# Laser7Clock.net
KiCad netlist of a schematic drawn in EAGLE
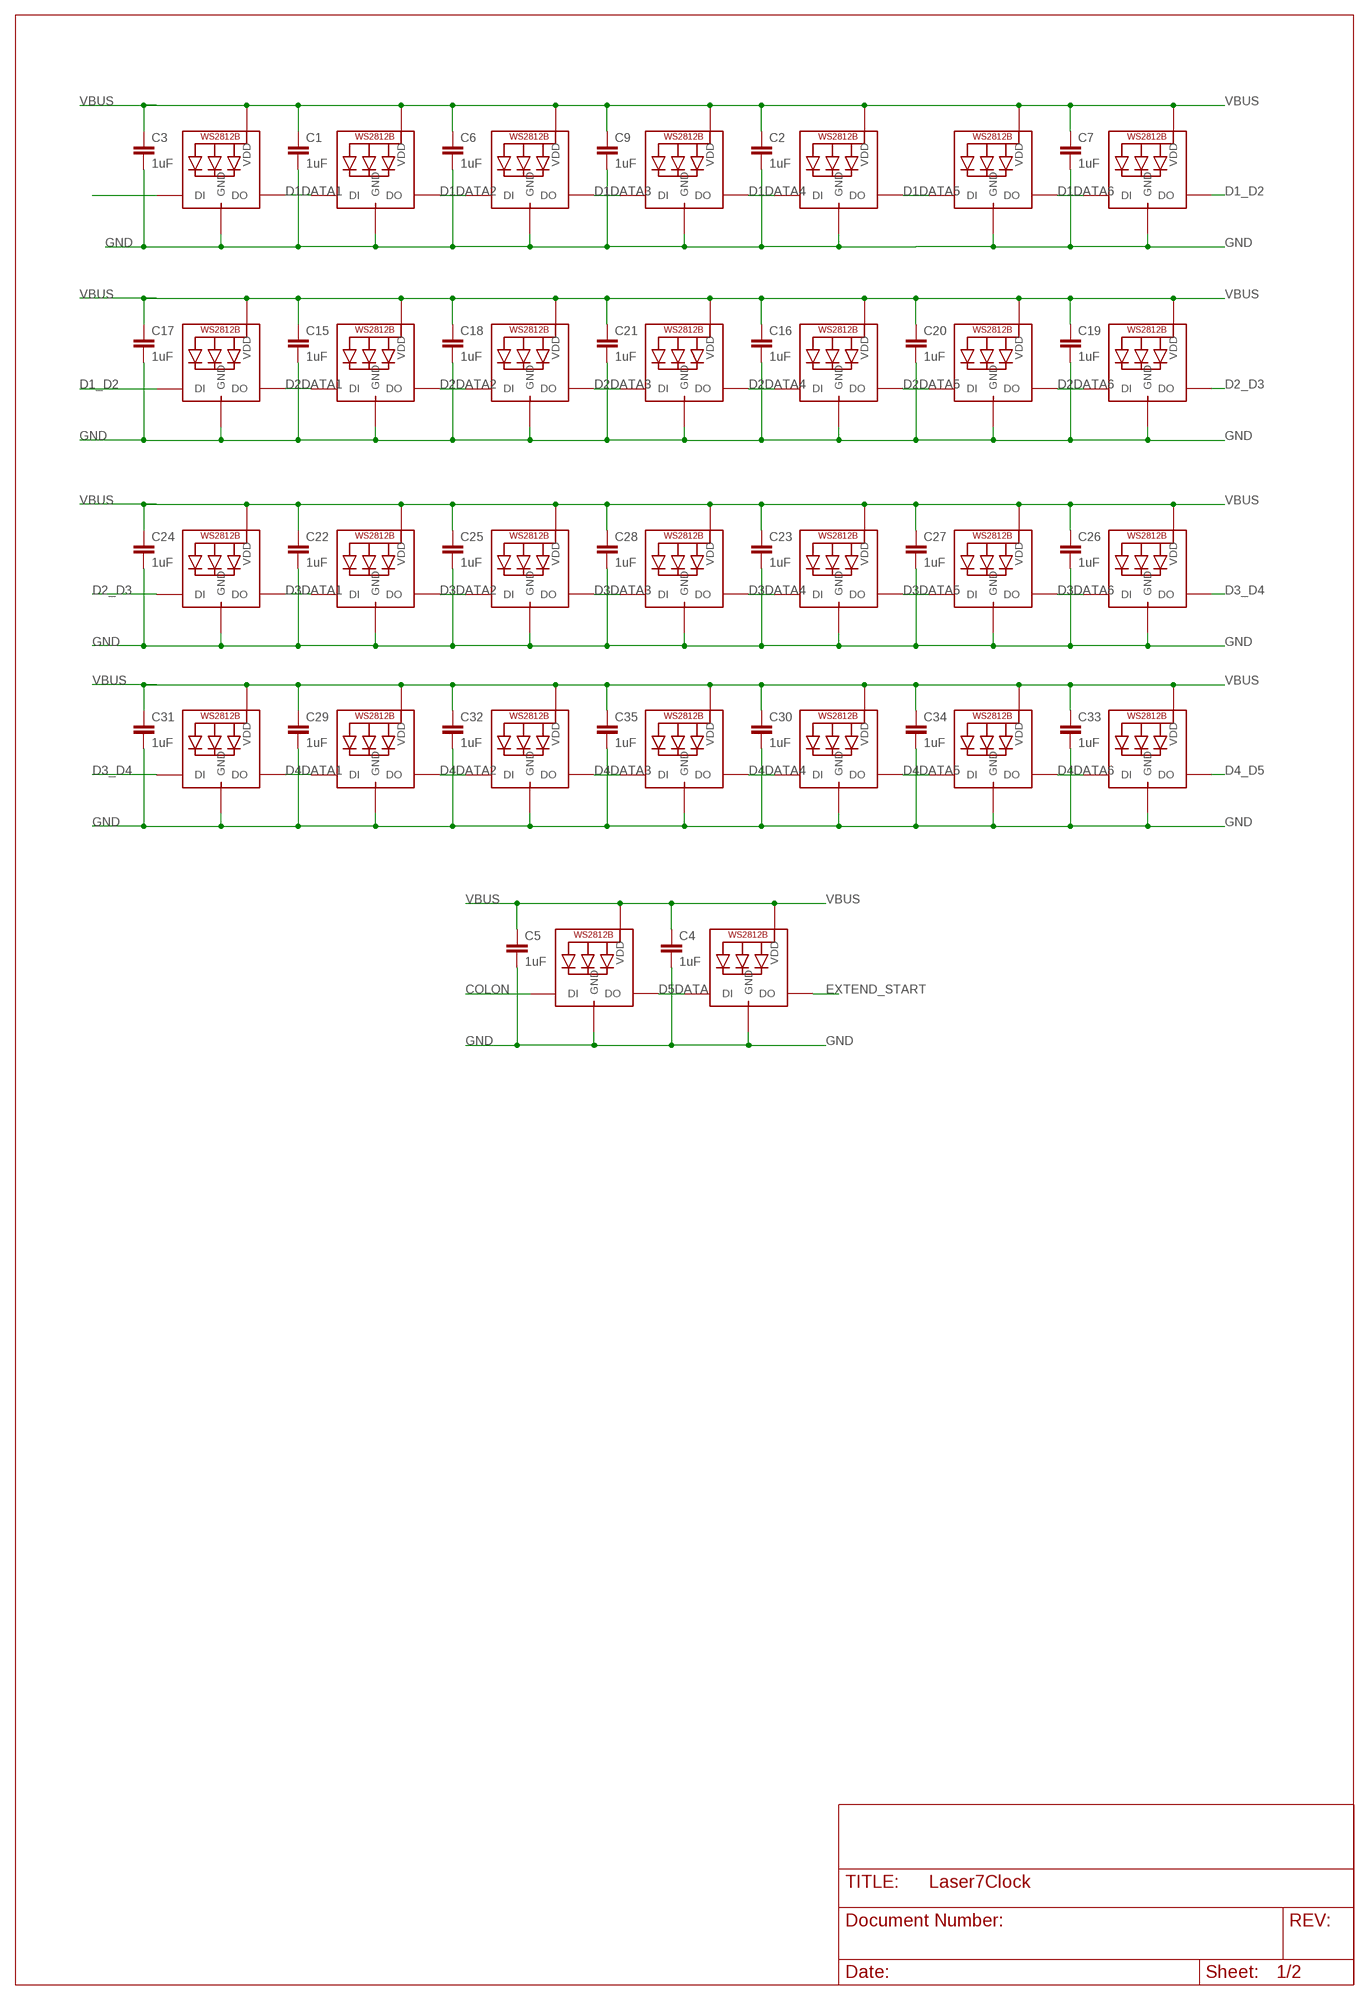
[diagram p0: schematic, sheet 1]
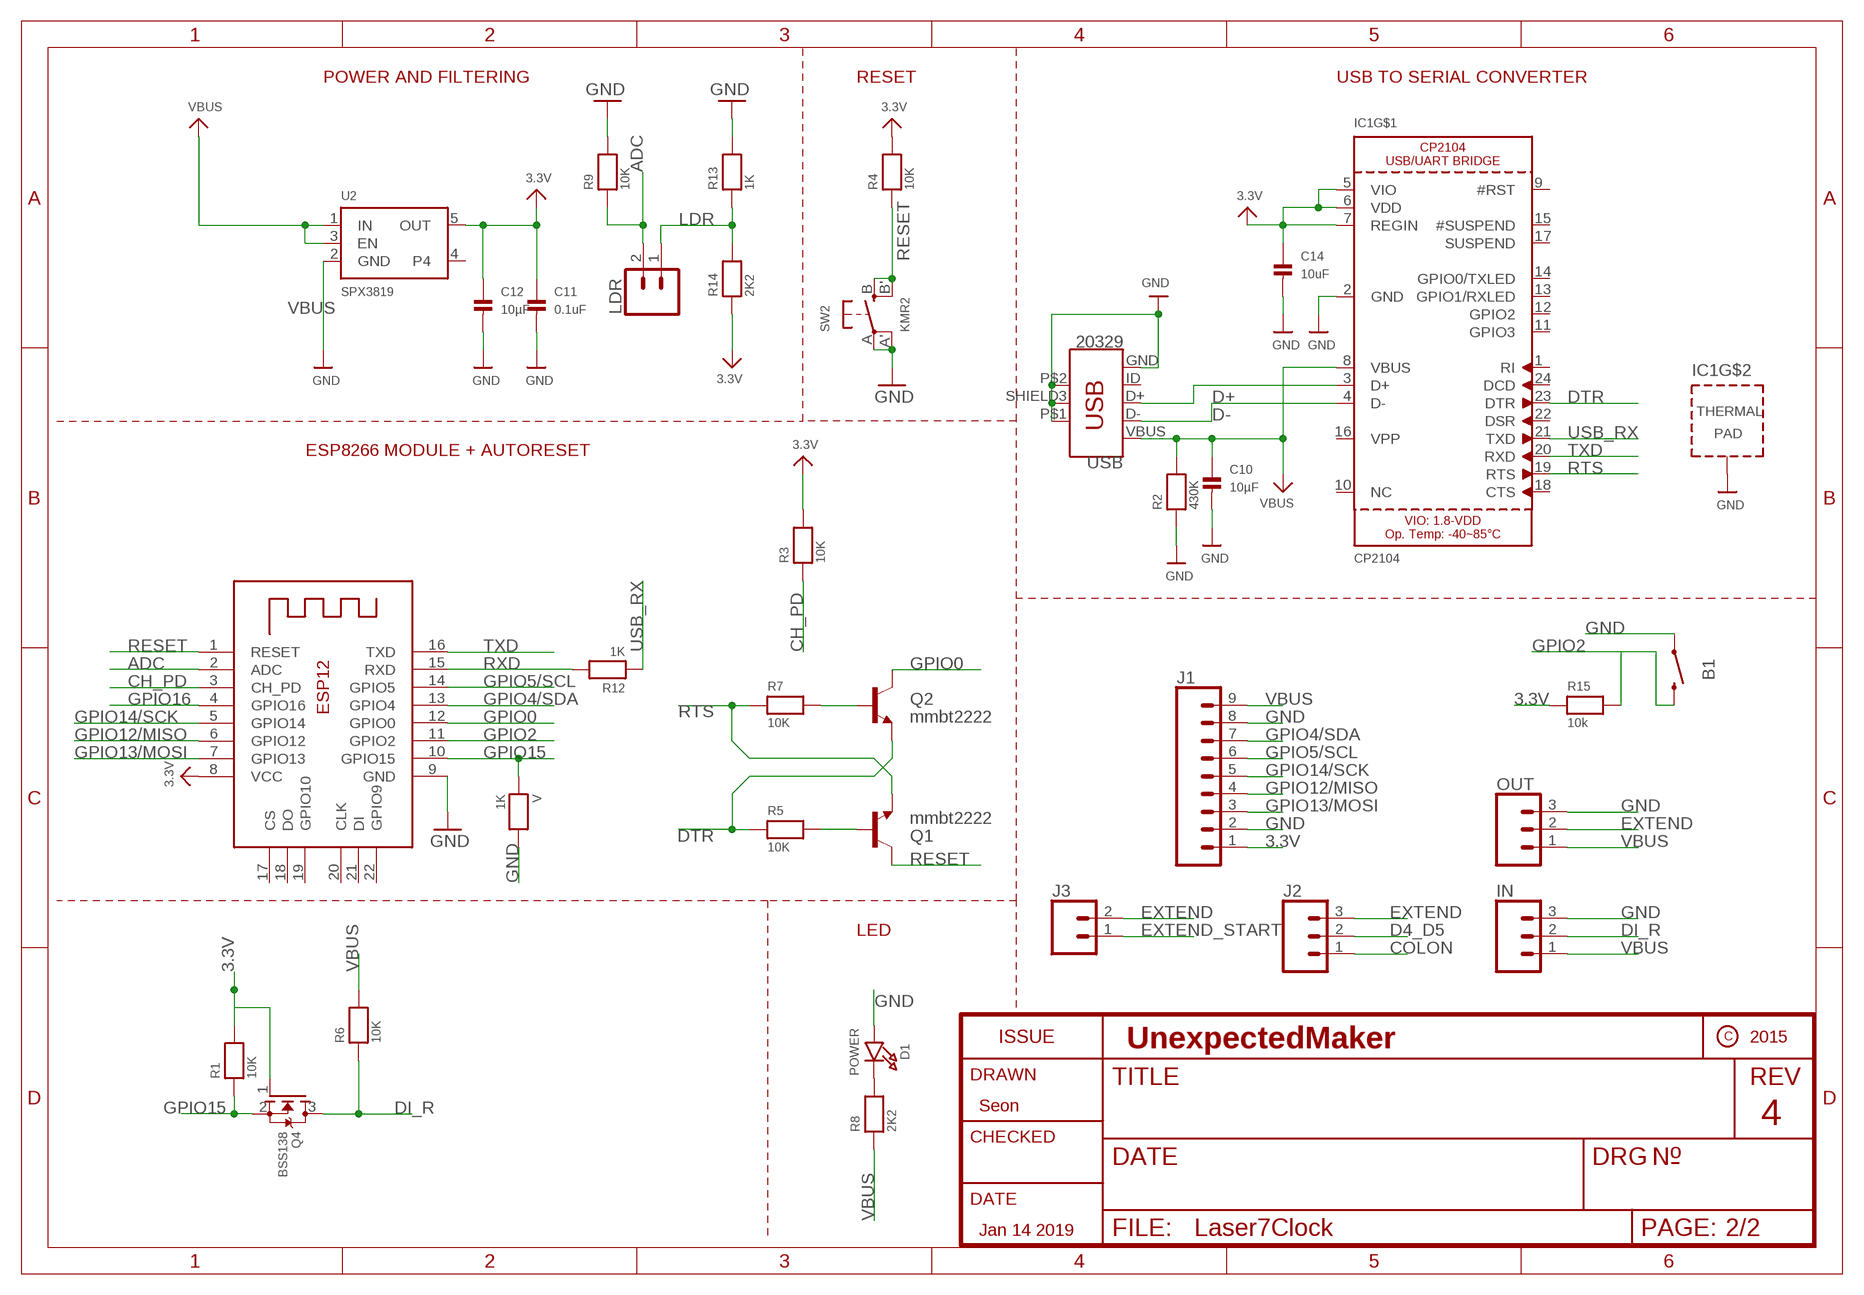
[diagram p1: schematic, sheet 2]

(export (version "E")
  (design (tool "Eeschema 10.0.6"))
  (components
    (comp (ref "B1")
      (value "MOMENTARY-SWITCH-SPST-PTH-RIGHT-ANGLE-KIT")
      (footprint "eagle-import:TACTILE_SWITCH_PTH_RIGHT_ANGLE_KIT")
      (libsource (lib "eagle-import") (part "MOMENTARY-SWITCH-SPST-PTH-RIGHT-ANGLE-KIT"))
    )
    (comp (ref "C10")
      (value "10µF")
      (footprint "eagle-import:_0805MP")
      (libsource (lib "eagle-import") (part "CAP_CERAMIC_0805MP"))
    )
    (comp (ref "C11")
      (value "0.1uF")
      (footprint "eagle-import:_0805MP")
      (libsource (lib "eagle-import") (part "CAP_CERAMIC_0805MP"))
    )
    (comp (ref "C12")
      (value "10µF")
      (footprint "eagle-import:_0805MP")
      (libsource (lib "eagle-import") (part "CAP_CERAMIC_0805MP"))
    )
    (comp (ref "C14")
      (value "10uF")
      (footprint "eagle-import:_0805MP")
      (libsource (lib "eagle-import") (part "CAP_CERAMIC_0805MP"))
    )
    (comp (ref "D1")
      (value "POWER")
      (footprint "eagle-import:CHIPLED_0805_NOOUTLINE")
      (libsource (lib "eagle-import") (part "LED0805_NOOUTLINE"))
    )
    (comp (ref "IC1")
      (value "CP2104")
      (footprint "eagle-import:QFN24_4MM_SMSC")
      (libsource (lib "eagle-import") (part "CP2104"))
    )
    (comp (ref "IN")
      (value "CONN_03LONGPADS")
      (footprint "eagle-import:1X03_LONGPADS")
      (libsource (lib "eagle-import") (part "CONN_03LONGPADS"))
    )
    (comp (ref "J1")
      (value "CONN_09NO_SILK")
      (footprint "eagle-import:1X09_NO_SILK")
      (libsource (lib "eagle-import") (part "CONN_09NO_SILK"))
    )
    (comp (ref "J2")
      (value "CONN_031X03_NO_SILK")
      (footprint "eagle-import:1X03_NO_SILK")
      (libsource (lib "eagle-import") (part "CONN_031X03_NO_SILK"))
    )
    (comp (ref "J3")
      (value "CONN_021X02_NO_SILK")
      (footprint "eagle-import:1X02_NO_SILK")
      (libsource (lib "eagle-import") (part "CONN_021X02_NO_SILK"))
    )
    (comp (ref "LDR")
      (value "CONN_021X02_NO_SILK")
      (footprint "eagle-import:1X02_NO_SILK")
      (libsource (lib "eagle-import") (part "CONN_021X02_NO_SILK"))
    )
    (comp (ref "OUT")
      (value "CONN_03LONGPADS")
      (footprint "eagle-import:1X03_LONGPADS")
      (libsource (lib "eagle-import") (part "CONN_03LONGPADS"))
    )
    (comp (ref "Q1")
      (value "mmbt2222")
      (footprint "eagle-import:SOT23-3")
      (libsource (lib "eagle-import") (part "TRANSISTOR_NPNSOT23-3"))
    )
    (comp (ref "Q2")
      (value "mmbt2222")
      (footprint "eagle-import:SOT23-3")
      (libsource (lib "eagle-import") (part "TRANSISTOR_NPNSOT23-3"))
    )
    (comp (ref "Q4")
      (value "BSS138")
      (footprint "eagle-import:SOT23-R")
      (libsource (lib "eagle-import") (part "MOSFET-NREFLOW"))
    )
    (comp (ref "R1")
      (value "10K")
      (footprint "eagle-import:_0603MP")
      (libsource (lib "eagle-import") (part "RESISTOR_0603MP"))
    )
    (comp (ref "R2")
      (value "430K")
      (footprint "eagle-import:_0805MP")
      (libsource (lib "eagle-import") (part "RESISTOR_0805MP"))
    )
    (comp (ref "R3")
      (value "10K")
      (footprint "eagle-import:_0603MP")
      (libsource (lib "eagle-import") (part "RESISTOR_0603MP"))
    )
    (comp (ref "R4")
      (value "10K")
      (footprint "eagle-import:_0603MP")
      (libsource (lib "eagle-import") (part "RESISTOR_0603MP"))
    )
    (comp (ref "R5")
      (value "10K")
      (footprint "eagle-import:_0603MP")
      (libsource (lib "eagle-import") (part "RESISTOR_0603MP"))
    )
    (comp (ref "R6")
      (value "10K")
      (footprint "eagle-import:_0603MP")
      (libsource (lib "eagle-import") (part "RESISTOR_0603MP"))
    )
    (comp (ref "R7")
      (value "10K")
      (footprint "eagle-import:_0603MP")
      (libsource (lib "eagle-import") (part "RESISTOR_0603MP"))
    )
    (comp (ref "R8")
      (value "2K2")
      (footprint "eagle-import:_0805MP")
      (libsource (lib "eagle-import") (part "RESISTOR_0805MP"))
    )
    (comp (ref "R9")
      (value "10K")
      (footprint "eagle-import:_0805MP")
      (libsource (lib "eagle-import") (part "RESISTOR_0805MP"))
    )
    (comp (ref "R12")
      (value "1K")
      (footprint "eagle-import:_0603MP")
      (libsource (lib "eagle-import") (part "RESISTOR_0603MP"))
    )
    (comp (ref "R13")
      (value "1K")
      (footprint "eagle-import:_0805MP")
      (libsource (lib "eagle-import") (part "RESISTOR_0805MP"))
    )
    (comp (ref "R14")
      (value "2K2")
      (footprint "eagle-import:_0805MP")
      (libsource (lib "eagle-import") (part "RESISTOR_0805MP"))
    )
    (comp (ref "R15")
      (value "10k")
      (footprint "eagle-import:_0603MP")
      (libsource (lib "eagle-import") (part "RESISTOR_0603MP"))
    )
    (comp (ref "SW2")
      (value "KMR2")
      (footprint "eagle-import:BTN_KMR2_4.6X2.8")
      (libsource (lib "eagle-import") (part "SWITCH_TACT_SMT4.6X2.8"))
    )
    (comp (ref "U2")
      (value "SPX3819")
      (footprint "eagle-import:SOT23-5")
      (libsource (lib "eagle-import") (part "VREG_SOT23-5"))
    )
    (comp (ref "USB")
      (value "20329")
      (footprint "eagle-import:USB-B-MICRO-SMD")
      (libsource (lib "eagle-import") (part "TINYPICO_USB_FEMALE-SMT"))
    )
    (comp (ref "V")
      (value "1K")
      (footprint "eagle-import:_0603MP")
      (libsource (lib "eagle-import") (part "RESISTOR_0603MP"))
    )
    (comp (ref "X2")
      (value "ESP-12")
      (footprint "eagle-import:ESP-12E")
      (libsource (lib "eagle-import") (part "ESP-12E"))
    )
    (comp (ref "C1")
      (value "1uF")
      (footprint "eagle-import:C0805K")
      (libsource (lib "eagle-import") (part "C-EUC0805K"))
    )
    (comp (ref "C2")
      (value "1uF")
      (footprint "eagle-import:C0805K")
      (libsource (lib "eagle-import") (part "C-EUC0805K"))
    )
    (comp (ref "C3")
      (value "1uF")
      (footprint "eagle-import:C0805K")
      (libsource (lib "eagle-import") (part "C-EUC0805K"))
    )
    (comp (ref "C4")
      (value "1uF")
      (footprint "eagle-import:C0805K")
      (libsource (lib "eagle-import") (part "C-EUC0805K"))
    )
    (comp (ref "C5")
      (value "1uF")
      (footprint "eagle-import:C0805K")
      (libsource (lib "eagle-import") (part "C-EUC0805K"))
    )
    (comp (ref "C6")
      (value "1uF")
      (footprint "eagle-import:C0805K")
      (libsource (lib "eagle-import") (part "C-EUC0805K"))
    )
    (comp (ref "C7")
      (value "1uF")
      (footprint "eagle-import:C0805K")
      (libsource (lib "eagle-import") (part "C-EUC0805K"))
    )
    (comp (ref "C9")
      (value "1uF")
      (footprint "eagle-import:C0805K")
      (libsource (lib "eagle-import") (part "C-EUC0805K"))
    )
    (comp (ref "C15")
      (value "1uF")
      (footprint "eagle-import:C0805K")
      (libsource (lib "eagle-import") (part "C-EUC0805K"))
    )
    (comp (ref "C16")
      (value "1uF")
      (footprint "eagle-import:C0805K")
      (libsource (lib "eagle-import") (part "C-EUC0805K"))
    )
    (comp (ref "C17")
      (value "1uF")
      (footprint "eagle-import:C0805K")
      (libsource (lib "eagle-import") (part "C-EUC0805K"))
    )
    (comp (ref "C18")
      (value "1uF")
      (footprint "eagle-import:C0805K")
      (libsource (lib "eagle-import") (part "C-EUC0805K"))
    )
    (comp (ref "C19")
      (value "1uF")
      (footprint "eagle-import:C0805K")
      (libsource (lib "eagle-import") (part "C-EUC0805K"))
    )
    (comp (ref "C20")
      (value "1uF")
      (footprint "eagle-import:C0805K")
      (libsource (lib "eagle-import") (part "C-EUC0805K"))
    )
    (comp (ref "C21")
      (value "1uF")
      (footprint "eagle-import:C0805K")
      (libsource (lib "eagle-import") (part "C-EUC0805K"))
    )
    (comp (ref "C22")
      (value "1uF")
      (footprint "eagle-import:C0805K")
      (libsource (lib "eagle-import") (part "C-EUC0805K"))
    )
    (comp (ref "C23")
      (value "1uF")
      (footprint "eagle-import:C0805K")
      (libsource (lib "eagle-import") (part "C-EUC0805K"))
    )
    (comp (ref "C24")
      (value "1uF")
      (footprint "eagle-import:C0805K")
      (libsource (lib "eagle-import") (part "C-EUC0805K"))
    )
    (comp (ref "C25")
      (value "1uF")
      (footprint "eagle-import:C0805K")
      (libsource (lib "eagle-import") (part "C-EUC0805K"))
    )
    (comp (ref "C26")
      (value "1uF")
      (footprint "eagle-import:C0805K")
      (libsource (lib "eagle-import") (part "C-EUC0805K"))
    )
    (comp (ref "C27")
      (value "1uF")
      (footprint "eagle-import:C0805K")
      (libsource (lib "eagle-import") (part "C-EUC0805K"))
    )
    (comp (ref "C28")
      (value "1uF")
      (footprint "eagle-import:C0805K")
      (libsource (lib "eagle-import") (part "C-EUC0805K"))
    )
    (comp (ref "C29")
      (value "1uF")
      (footprint "eagle-import:C0805K")
      (libsource (lib "eagle-import") (part "C-EUC0805K"))
    )
    (comp (ref "C30")
      (value "1uF")
      (footprint "eagle-import:C0805K")
      (libsource (lib "eagle-import") (part "C-EUC0805K"))
    )
    (comp (ref "C31")
      (value "1uF")
      (footprint "eagle-import:C0805K")
      (libsource (lib "eagle-import") (part "C-EUC0805K"))
    )
    (comp (ref "C32")
      (value "1uF")
      (footprint "eagle-import:C0805K")
      (libsource (lib "eagle-import") (part "C-EUC0805K"))
    )
    (comp (ref "C33")
      (value "1uF")
      (footprint "eagle-import:C0805K")
      (libsource (lib "eagle-import") (part "C-EUC0805K"))
    )
    (comp (ref "C34")
      (value "1uF")
      (footprint "eagle-import:C0805K")
      (libsource (lib "eagle-import") (part "C-EUC0805K"))
    )
    (comp (ref "C35")
      (value "1uF")
      (footprint "eagle-import:C0805K")
      (libsource (lib "eagle-import") (part "C-EUC0805K"))
    )
    (comp (ref "D1L1")
      (value "WS2812B5050")
      (footprint "eagle-import:WS2812B")
      (libsource (lib "eagle-import") (part "WS2812B5050"))
    )
    (comp (ref "D1L2")
      (value "WS2812B5050")
      (footprint "eagle-import:WS2812B")
      (libsource (lib "eagle-import") (part "WS2812B5050"))
    )
    (comp (ref "D1L3")
      (value "WS2812B5050")
      (footprint "eagle-import:WS2812B")
      (libsource (lib "eagle-import") (part "WS2812B5050"))
    )
    (comp (ref "D1L4")
      (value "WS2812B5050")
      (footprint "eagle-import:WS2812B")
      (libsource (lib "eagle-import") (part "WS2812B5050"))
    )
    (comp (ref "D1L5")
      (value "WS2812B5050")
      (footprint "eagle-import:WS2812B")
      (libsource (lib "eagle-import") (part "WS2812B5050"))
    )
    (comp (ref "D1L6")
      (value "WS2812B5050")
      (footprint "eagle-import:WS2812B")
      (libsource (lib "eagle-import") (part "WS2812B5050"))
    )
    (comp (ref "D1L7")
      (value "WS2812B5050")
      (footprint "eagle-import:WS2812B")
      (libsource (lib "eagle-import") (part "WS2812B5050"))
    )
    (comp (ref "D2L1")
      (value "WS2812B5050")
      (footprint "eagle-import:WS2812B")
      (libsource (lib "eagle-import") (part "WS2812B5050"))
    )
    (comp (ref "D2L2")
      (value "WS2812B5050")
      (footprint "eagle-import:WS2812B")
      (libsource (lib "eagle-import") (part "WS2812B5050"))
    )
    (comp (ref "D2L3")
      (value "WS2812B5050")
      (footprint "eagle-import:WS2812B")
      (libsource (lib "eagle-import") (part "WS2812B5050"))
    )
    (comp (ref "D2L4")
      (value "WS2812B5050")
      (footprint "eagle-import:WS2812B")
      (libsource (lib "eagle-import") (part "WS2812B5050"))
    )
    (comp (ref "D2L5")
      (value "WS2812B5050")
      (footprint "eagle-import:WS2812B")
      (libsource (lib "eagle-import") (part "WS2812B5050"))
    )
    (comp (ref "D2L6")
      (value "WS2812B5050")
      (footprint "eagle-import:WS2812B")
      (libsource (lib "eagle-import") (part "WS2812B5050"))
    )
    (comp (ref "D2L7")
      (value "WS2812B5050")
      (footprint "eagle-import:WS2812B")
      (libsource (lib "eagle-import") (part "WS2812B5050"))
    )
    (comp (ref "D3L1")
      (value "WS2812B5050")
      (footprint "eagle-import:WS2812B")
      (libsource (lib "eagle-import") (part "WS2812B5050"))
    )
    (comp (ref "D3L2")
      (value "WS2812B5050")
      (footprint "eagle-import:WS2812B")
      (libsource (lib "eagle-import") (part "WS2812B5050"))
    )
    (comp (ref "D3L3")
      (value "WS2812B5050")
      (footprint "eagle-import:WS2812B")
      (libsource (lib "eagle-import") (part "WS2812B5050"))
    )
    (comp (ref "D3L4")
      (value "WS2812B5050")
      (footprint "eagle-import:WS2812B")
      (libsource (lib "eagle-import") (part "WS2812B5050"))
    )
    (comp (ref "D3L5")
      (value "WS2812B5050")
      (footprint "eagle-import:WS2812B")
      (libsource (lib "eagle-import") (part "WS2812B5050"))
    )
    (comp (ref "D3L6")
      (value "WS2812B5050")
      (footprint "eagle-import:WS2812B")
      (libsource (lib "eagle-import") (part "WS2812B5050"))
    )
    (comp (ref "D3L7")
      (value "WS2812B5050")
      (footprint "eagle-import:WS2812B")
      (libsource (lib "eagle-import") (part "WS2812B5050"))
    )
    (comp (ref "D4L1")
      (value "WS2812B5050")
      (footprint "eagle-import:WS2812B")
      (libsource (lib "eagle-import") (part "WS2812B5050"))
    )
    (comp (ref "D4L2")
      (value "WS2812B5050")
      (footprint "eagle-import:WS2812B")
      (libsource (lib "eagle-import") (part "WS2812B5050"))
    )
    (comp (ref "D4L3")
      (value "WS2812B5050")
      (footprint "eagle-import:WS2812B")
      (libsource (lib "eagle-import") (part "WS2812B5050"))
    )
    (comp (ref "D4L4")
      (value "WS2812B5050")
      (footprint "eagle-import:WS2812B")
      (libsource (lib "eagle-import") (part "WS2812B5050"))
    )
    (comp (ref "D4L5")
      (value "WS2812B5050")
      (footprint "eagle-import:WS2812B")
      (libsource (lib "eagle-import") (part "WS2812B5050"))
    )
    (comp (ref "D4L6")
      (value "WS2812B5050")
      (footprint "eagle-import:WS2812B")
      (libsource (lib "eagle-import") (part "WS2812B5050"))
    )
    (comp (ref "D4L7")
      (value "WS2812B5050")
      (footprint "eagle-import:WS2812B")
      (libsource (lib "eagle-import") (part "WS2812B5050"))
    )
    (comp (ref "LED1")
      (value "WS2812B5050")
      (footprint "eagle-import:WS2812B")
      (libsource (lib "eagle-import") (part "WS2812B5050"))
    )
    (comp (ref "LED2")
      (value "WS2812B5050")
      (footprint "eagle-import:WS2812B")
      (libsource (lib "eagle-import") (part "WS2812B5050"))
    )
  )
  (nets
    (net (code "1") (name "3.3V") (class "Default")
      (node (ref "C11") (pin "1") (pinfunction "P$1_1") (pintype "passive"))
      (node (ref "C12") (pin "1") (pinfunction "P$1_1") (pintype "passive"))
      (node (ref "C14") (pin "1") (pinfunction "P$1_1") (pintype "passive"))
      (node (ref "IC1") (pin "5") (pinfunction "VIO_5") (pintype "power_in"))
      (node (ref "IC1") (pin "6") (pinfunction "VDD_6") (pintype "power_in"))
      (node (ref "IC1") (pin "7") (pinfunction "REGIN_7") (pintype "power_in"))
      (node (ref "J1") (pin "1") (pinfunction "1_1") (pintype "passive"))
      (node (ref "Q4") (pin "1") (pinfunction "G_1") (pintype "bidirectional"))
      (node (ref "R1") (pin "2") (pinfunction "2_2") (pintype "passive"))
      (node (ref "R14") (pin "1") (pinfunction "1_1") (pintype "passive"))
      (node (ref "R15") (pin "1") (pinfunction "1_1") (pintype "passive"))
      (node (ref "R3") (pin "2") (pinfunction "2_2") (pintype "passive"))
      (node (ref "R4") (pin "2") (pinfunction "2_2") (pintype "passive"))
      (node (ref "U2") (pin "5") (pinfunction "OUT_5") (pintype "power_in"))
      (node (ref "X2") (pin "8") (pinfunction "VCC_8") (pintype "power_in"))
    )
    (net (code "2") (name "ADC") (class "Default")
      (node (ref "LDR") (pin "2") (pinfunction "2_2") (pintype "passive"))
      (node (ref "R9") (pin "1") (pinfunction "1_1") (pintype "passive"))
      (node (ref "X2") (pin "2") (pinfunction "ADC_2") (pintype "passive"))
    )
    (net (code "3") (name "CH_PD") (class "Default")
      (node (ref "R3") (pin "1") (pinfunction "1_1") (pintype "passive"))
      (node (ref "X2") (pin "3") (pinfunction "CH_PD_3") (pintype "input"))
    )
    (net (code "4") (name "COLON") (class "Default")
      (node (ref "J2") (pin "1") (pinfunction "1_1") (pintype "passive"))
      (node (ref "LED1") (pin "4-DIN") (pinfunction "DI_4-DIN") (pintype "input"))
    )
    (net (code "5") (name "D+") (class "Default")
      (node (ref "IC1") (pin "3") (pinfunction "D+_3") (pintype "bidirectional"))
      (node (ref "USB") (pin "D+") (pinfunction "D+_D+") (pintype "bidirectional"))
    )
    (net (code "6") (name "D-") (class "Default")
      (node (ref "IC1") (pin "4") (pinfunction "D-_4") (pintype "bidirectional"))
      (node (ref "USB") (pin "D-") (pinfunction "D-_D-") (pintype "bidirectional"))
    )
    (net (code "7") (name "D1DATA1") (class "Default")
      (node (ref "D1L1") (pin "2-DOUT") (pinfunction "DO_2-DOUT") (pintype "output"))
      (node (ref "D1L2") (pin "4-DIN") (pinfunction "DI_4-DIN") (pintype "input"))
    )
    (net (code "8") (name "D1DATA2") (class "Default")
      (node (ref "D1L2") (pin "2-DOUT") (pinfunction "DO_2-DOUT") (pintype "output"))
      (node (ref "D1L3") (pin "4-DIN") (pinfunction "DI_4-DIN") (pintype "input"))
    )
    (net (code "9") (name "D1DATA3") (class "Default")
      (node (ref "D1L3") (pin "2-DOUT") (pinfunction "DO_2-DOUT") (pintype "output"))
      (node (ref "D1L4") (pin "4-DIN") (pinfunction "DI_4-DIN") (pintype "input"))
    )
    (net (code "10") (name "D1DATA4") (class "Default")
      (node (ref "D1L4") (pin "2-DOUT") (pinfunction "DO_2-DOUT") (pintype "output"))
      (node (ref "D1L5") (pin "4-DIN") (pinfunction "DI_4-DIN") (pintype "input"))
    )
    (net (code "11") (name "D1DATA5") (class "Default")
      (node (ref "D1L5") (pin "2-DOUT") (pinfunction "DO_2-DOUT") (pintype "output"))
      (node (ref "D1L6") (pin "4-DIN") (pinfunction "DI_4-DIN") (pintype "input"))
    )
    (net (code "12") (name "D1DATA6") (class "Default")
      (node (ref "D1L6") (pin "2-DOUT") (pinfunction "DO_2-DOUT") (pintype "output"))
      (node (ref "D1L7") (pin "4-DIN") (pinfunction "DI_4-DIN") (pintype "input"))
    )
    (net (code "13") (name "D1_D2") (class "Default")
      (node (ref "D1L7") (pin "2-DOUT") (pinfunction "DO_2-DOUT") (pintype "output"))
      (node (ref "D2L1") (pin "4-DIN") (pinfunction "DI_4-DIN") (pintype "input"))
    )
    (net (code "14") (name "D2DATA1") (class "Default")
      (node (ref "D2L1") (pin "2-DOUT") (pinfunction "DO_2-DOUT") (pintype "output"))
      (node (ref "D2L2") (pin "4-DIN") (pinfunction "DI_4-DIN") (pintype "input"))
    )
    (net (code "15") (name "D2DATA2") (class "Default")
      (node (ref "D2L2") (pin "2-DOUT") (pinfunction "DO_2-DOUT") (pintype "output"))
      (node (ref "D2L3") (pin "4-DIN") (pinfunction "DI_4-DIN") (pintype "input"))
    )
    (net (code "16") (name "D2DATA3") (class "Default")
      (node (ref "D2L3") (pin "2-DOUT") (pinfunction "DO_2-DOUT") (pintype "output"))
      (node (ref "D2L4") (pin "4-DIN") (pinfunction "DI_4-DIN") (pintype "input"))
    )
    (net (code "17") (name "D2DATA4") (class "Default")
      (node (ref "D2L4") (pin "2-DOUT") (pinfunction "DO_2-DOUT") (pintype "output"))
      (node (ref "D2L5") (pin "4-DIN") (pinfunction "DI_4-DIN") (pintype "input"))
    )
    (net (code "18") (name "D2DATA5") (class "Default")
      (node (ref "D2L5") (pin "2-DOUT") (pinfunction "DO_2-DOUT") (pintype "output"))
      (node (ref "D2L6") (pin "4-DIN") (pinfunction "DI_4-DIN") (pintype "input"))
    )
    (net (code "19") (name "D2DATA6") (class "Default")
      (node (ref "D2L6") (pin "2-DOUT") (pinfunction "DO_2-DOUT") (pintype "output"))
      (node (ref "D2L7") (pin "4-DIN") (pinfunction "DI_4-DIN") (pintype "input"))
    )
    (net (code "20") (name "D2_D3") (class "Default")
      (node (ref "D2L7") (pin "2-DOUT") (pinfunction "DO_2-DOUT") (pintype "output"))
      (node (ref "D3L1") (pin "4-DIN") (pinfunction "DI_4-DIN") (pintype "input"))
    )
    (net (code "21") (name "D3DATA1") (class "Default")
      (node (ref "D3L1") (pin "2-DOUT") (pinfunction "DO_2-DOUT") (pintype "output"))
      (node (ref "D3L2") (pin "4-DIN") (pinfunction "DI_4-DIN") (pintype "input"))
    )
    (net (code "22") (name "D3DATA2") (class "Default")
      (node (ref "D3L2") (pin "2-DOUT") (pinfunction "DO_2-DOUT") (pintype "output"))
      (node (ref "D3L3") (pin "4-DIN") (pinfunction "DI_4-DIN") (pintype "input"))
    )
    (net (code "23") (name "D3DATA3") (class "Default")
      (node (ref "D3L3") (pin "2-DOUT") (pinfunction "DO_2-DOUT") (pintype "output"))
      (node (ref "D3L4") (pin "4-DIN") (pinfunction "DI_4-DIN") (pintype "input"))
    )
    (net (code "24") (name "D3DATA4") (class "Default")
      (node (ref "D3L4") (pin "2-DOUT") (pinfunction "DO_2-DOUT") (pintype "output"))
      (node (ref "D3L5") (pin "4-DIN") (pinfunction "DI_4-DIN") (pintype "input"))
    )
    (net (code "25") (name "D3DATA5") (class "Default")
      (node (ref "D3L5") (pin "2-DOUT") (pinfunction "DO_2-DOUT") (pintype "output"))
      (node (ref "D3L6") (pin "4-DIN") (pinfunction "DI_4-DIN") (pintype "input"))
    )
    (net (code "26") (name "D3DATA6") (class "Default")
      (node (ref "D3L6") (pin "2-DOUT") (pinfunction "DO_2-DOUT") (pintype "output"))
      (node (ref "D3L7") (pin "4-DIN") (pinfunction "DI_4-DIN") (pintype "input"))
    )
    (net (code "27") (name "D3_D4") (class "Default")
      (node (ref "D3L7") (pin "2-DOUT") (pinfunction "DO_2-DOUT") (pintype "output"))
      (node (ref "D4L1") (pin "4-DIN") (pinfunction "DI_4-DIN") (pintype "input"))
    )
    (net (code "28") (name "D4DATA1") (class "Default")
      (node (ref "D4L1") (pin "2-DOUT") (pinfunction "DO_2-DOUT") (pintype "output"))
      (node (ref "D4L2") (pin "4-DIN") (pinfunction "DI_4-DIN") (pintype "input"))
    )
    (net (code "29") (name "D4DATA2") (class "Default")
      (node (ref "D4L2") (pin "2-DOUT") (pinfunction "DO_2-DOUT") (pintype "output"))
      (node (ref "D4L3") (pin "4-DIN") (pinfunction "DI_4-DIN") (pintype "input"))
    )
    (net (code "30") (name "D4DATA3") (class "Default")
      (node (ref "D4L3") (pin "2-DOUT") (pinfunction "DO_2-DOUT") (pintype "output"))
      (node (ref "D4L4") (pin "4-DIN") (pinfunction "DI_4-DIN") (pintype "input"))
    )
    (net (code "31") (name "D4DATA4") (class "Default")
      (node (ref "D4L4") (pin "2-DOUT") (pinfunction "DO_2-DOUT") (pintype "output"))
      (node (ref "D4L5") (pin "4-DIN") (pinfunction "DI_4-DIN") (pintype "input"))
    )
    (net (code "32") (name "D4DATA5") (class "Default")
      (node (ref "D4L5") (pin "2-DOUT") (pinfunction "DO_2-DOUT") (pintype "output"))
      (node (ref "D4L6") (pin "4-DIN") (pinfunction "DI_4-DIN") (pintype "input"))
    )
    (net (code "33") (name "D4DATA6") (class "Default")
      (node (ref "D4L6") (pin "2-DOUT") (pinfunction "DO_2-DOUT") (pintype "output"))
      (node (ref "D4L7") (pin "4-DIN") (pinfunction "DI_4-DIN") (pintype "input"))
    )
    (net (code "34") (name "D4_D5") (class "Default")
      (node (ref "D4L7") (pin "2-DOUT") (pinfunction "DO_2-DOUT") (pintype "output"))
      (node (ref "J2") (pin "2") (pinfunction "2_2") (pintype "passive"))
    )
    (net (code "35") (name "D5DATA") (class "Default")
      (node (ref "LED1") (pin "2-DOUT") (pinfunction "DO_2-DOUT") (pintype "output"))
      (node (ref "LED2") (pin "4-DIN") (pinfunction "DI_4-DIN") (pintype "input"))
    )
    (net (code "36") (name "DI_R") (class "Default")
      (node (ref "D1L1") (pin "4-DIN") (pinfunction "DI_4-DIN") (pintype "input"))
      (node (ref "IN") (pin "2") (pinfunction "2_2") (pintype "passive"))
      (node (ref "Q4") (pin "3") (pinfunction "D_3") (pintype "bidirectional"))
      (node (ref "R6") (pin "1") (pinfunction "1_1") (pintype "passive"))
    )
    (net (code "37") (name "DTR") (class "Default")
      (node (ref "IC1") (pin "23") (pinfunction "DTR_23") (pintype "output"))
      (node (ref "Q2") (pin "2") (pinfunction "E_2") (pintype "passive"))
      (node (ref "R5") (pin "1") (pinfunction "1_1") (pintype "passive"))
    )
    (net (code "38") (name "EXTEND") (class "Default")
      (node (ref "J2") (pin "3") (pinfunction "3_3") (pintype "passive"))
      (node (ref "J3") (pin "2") (pinfunction "2_2") (pintype "passive"))
      (node (ref "OUT") (pin "2") (pinfunction "2_2") (pintype "passive"))
    )
    (net (code "39") (name "EXTEND_START") (class "Default")
      (node (ref "J3") (pin "1") (pinfunction "1_1") (pintype "passive"))
      (node (ref "LED2") (pin "2-DOUT") (pinfunction "DO_2-DOUT") (pintype "output"))
    )
    (net (code "40") (name "GND") (class "Default")
      (node (ref "B1") (pin "1") (pinfunction "1_1") (pintype "passive"))
      (node (ref "C1") (pin "2") (pinfunction "2_2") (pintype "passive"))
      (node (ref "C10") (pin "2") (pinfunction "P$2_2") (pintype "passive"))
      (node (ref "C11") (pin "2") (pinfunction "P$2_2") (pintype "passive"))
      (node (ref "C12") (pin "2") (pinfunction "P$2_2") (pintype "passive"))
      (node (ref "C14") (pin "2") (pinfunction "P$2_2") (pintype "passive"))
      (node (ref "C15") (pin "2") (pinfunction "2_2") (pintype "passive"))
      (node (ref "C16") (pin "2") (pinfunction "2_2") (pintype "passive"))
      (node (ref "C17") (pin "2") (pinfunction "2_2") (pintype "passive"))
      (node (ref "C18") (pin "2") (pinfunction "2_2") (pintype "passive"))
      (node (ref "C19") (pin "2") (pinfunction "2_2") (pintype "passive"))
      (node (ref "C2") (pin "2") (pinfunction "2_2") (pintype "passive"))
      (node (ref "C20") (pin "2") (pinfunction "2_2") (pintype "passive"))
      (node (ref "C21") (pin "2") (pinfunction "2_2") (pintype "passive"))
      (node (ref "C22") (pin "2") (pinfunction "2_2") (pintype "passive"))
      (node (ref "C23") (pin "2") (pinfunction "2_2") (pintype "passive"))
      (node (ref "C24") (pin "2") (pinfunction "2_2") (pintype "passive"))
      (node (ref "C25") (pin "2") (pinfunction "2_2") (pintype "passive"))
      (node (ref "C26") (pin "2") (pinfunction "2_2") (pintype "passive"))
      (node (ref "C27") (pin "2") (pinfunction "2_2") (pintype "passive"))
      (node (ref "C28") (pin "2") (pinfunction "2_2") (pintype "passive"))
      (node (ref "C29") (pin "2") (pinfunction "2_2") (pintype "passive"))
      (node (ref "C3") (pin "2") (pinfunction "2_2") (pintype "passive"))
      (node (ref "C30") (pin "2") (pinfunction "2_2") (pintype "passive"))
      (node (ref "C31") (pin "2") (pinfunction "2_2") (pintype "passive"))
      (node (ref "C32") (pin "2") (pinfunction "2_2") (pintype "passive"))
      (node (ref "C33") (pin "2") (pinfunction "2_2") (pintype "passive"))
      (node (ref "C34") (pin "2") (pinfunction "2_2") (pintype "passive"))
      (node (ref "C35") (pin "2") (pinfunction "2_2") (pintype "passive"))
      (node (ref "C4") (pin "2") (pinfunction "2_2") (pintype "passive"))
      (node (ref "C5") (pin "2") (pinfunction "2_2") (pintype "passive"))
      (node (ref "C6") (pin "2") (pinfunction "2_2") (pintype "passive"))
      (node (ref "C7") (pin "2") (pinfunction "2_2") (pintype "passive"))
      (node (ref "C9") (pin "2") (pinfunction "2_2") (pintype "passive"))
      (node (ref "D1") (pin "A") (pinfunction "A_A") (pintype "passive"))
      (node (ref "D1L1") (pin "3-GND") (pinfunction "GND_3-GND") (pintype "power_in"))
      (node (ref "D1L2") (pin "3-GND") (pinfunction "GND_3-GND") (pintype "power_in"))
      (node (ref "D1L3") (pin "3-GND") (pinfunction "GND_3-GND") (pintype "power_in"))
      (node (ref "D1L4") (pin "3-GND") (pinfunction "GND_3-GND") (pintype "power_in"))
      (node (ref "D1L5") (pin "3-GND") (pinfunction "GND_3-GND") (pintype "power_in"))
      (node (ref "D1L6") (pin "3-GND") (pinfunction "GND_3-GND") (pintype "power_in"))
      (node (ref "D1L7") (pin "3-GND") (pinfunction "GND_3-GND") (pintype "power_in"))
      (node (ref "D2L1") (pin "3-GND") (pinfunction "GND_3-GND") (pintype "power_in"))
      (node (ref "D2L2") (pin "3-GND") (pinfunction "GND_3-GND") (pintype "power_in"))
      (node (ref "D2L3") (pin "3-GND") (pinfunction "GND_3-GND") (pintype "power_in"))
      (node (ref "D2L4") (pin "3-GND") (pinfunction "GND_3-GND") (pintype "power_in"))
      (node (ref "D2L5") (pin "3-GND") (pinfunction "GND_3-GND") (pintype "power_in"))
      (node (ref "D2L6") (pin "3-GND") (pinfunction "GND_3-GND") (pintype "power_in"))
      (node (ref "D2L7") (pin "3-GND") (pinfunction "GND_3-GND") (pintype "power_in"))
      (node (ref "D3L1") (pin "3-GND") (pinfunction "GND_3-GND") (pintype "power_in"))
      (node (ref "D3L2") (pin "3-GND") (pinfunction "GND_3-GND") (pintype "power_in"))
      (node (ref "D3L3") (pin "3-GND") (pinfunction "GND_3-GND") (pintype "power_in"))
      (node (ref "D3L4") (pin "3-GND") (pinfunction "GND_3-GND") (pintype "power_in"))
      (node (ref "D3L5") (pin "3-GND") (pinfunction "GND_3-GND") (pintype "power_in"))
      (node (ref "D3L6") (pin "3-GND") (pinfunction "GND_3-GND") (pintype "power_in"))
      (node (ref "D3L7") (pin "3-GND") (pinfunction "GND_3-GND") (pintype "power_in"))
      (node (ref "D4L1") (pin "3-GND") (pinfunction "GND_3-GND") (pintype "power_in"))
      (node (ref "D4L2") (pin "3-GND") (pinfunction "GND_3-GND") (pintype "power_in"))
      (node (ref "D4L3") (pin "3-GND") (pinfunction "GND_3-GND") (pintype "power_in"))
      (node (ref "D4L4") (pin "3-GND") (pinfunction "GND_3-GND") (pintype "power_in"))
      (node (ref "D4L5") (pin "3-GND") (pinfunction "GND_3-GND") (pintype "power_in"))
      (node (ref "D4L6") (pin "3-GND") (pinfunction "GND_3-GND") (pintype "power_in"))
      (node (ref "D4L7") (pin "3-GND") (pinfunction "GND_3-GND") (pintype "power_in"))
      (node (ref "IC1") (pin "2") (pinfunction "GND_2") (pintype "power_in"))
      (node (ref "IC1") (pin "THERM") (pinfunction "TP_THERM") (pintype "power_in"))
      (node (ref "IN") (pin "3") (pinfunction "3_3") (pintype "passive"))
      (node (ref "J1") (pin "2") (pinfunction "2_2") (pintype "passive"))
      (node (ref "J1") (pin "8") (pinfunction "8_8") (pintype "passive"))
      (node (ref "LED1") (pin "3-GND") (pinfunction "GND_3-GND") (pintype "power_in"))
      (node (ref "LED2") (pin "3-GND") (pinfunction "GND_3-GND") (pintype "power_in"))
      (node (ref "OUT") (pin "3") (pinfunction "3_3") (pintype "passive"))
      (node (ref "R13") (pin "2") (pinfunction "2_2") (pintype "passive"))
      (node (ref "R2") (pin "1") (pinfunction "1_1") (pintype "passive"))
      (node (ref "R9") (pin "2") (pinfunction "2_2") (pintype "passive"))
      (node (ref "SW2") (pin "A") (pinfunction "P_A") (pintype "passive"))
      (node (ref "SW2") (pin "A'") (pinfunction "P1_A'") (pintype "passive"))
      (node (ref "U2") (pin "2") (pinfunction "GND_2") (pintype "power_in"))
      (node (ref "USB") (pin "GND") (pinfunction "GND_GND") (pintype "power_in"))
      (node (ref "USB") (pin "P$1") (pinfunction "SHIELD1_P$1") (pintype "bidirectional"))
      (node (ref "USB") (pin "P$2") (pinfunction "SHIELD2_P$2") (pintype "bidirectional"))
      (node (ref "USB") (pin "SHIELD3") (pinfunction "SHIELD_SHIELD3") (pintype "bidirectional"))
      (node (ref "V") (pin "2") (pinfunction "2_2") (pintype "passive"))
      (node (ref "X2") (pin "9") (pinfunction "GND_9") (pintype "power_in"))
    )
    (net (code "41") (name "GPIO0") (class "Default")
      (node (ref "Q2") (pin "3") (pinfunction "C_3") (pintype "passive"))
      (node (ref "X2") (pin "12") (pinfunction "GPIO0_12") (pintype "bidirectional"))
    )
    (net (code "42") (name "GPIO2") (class "Default")
      (node (ref "B1") (pin "2") (pinfunction "2_2") (pintype "passive"))
      (node (ref "R15") (pin "2") (pinfunction "2_2") (pintype "passive"))
      (node (ref "X2") (pin "11") (pinfunction "GPIO2_11") (pintype "bidirectional"))
    )
    (net (code "43") (name "GPIO4{slash}SDA") (class "Default")
      (node (ref "J1") (pin "7") (pinfunction "7_7") (pintype "passive"))
      (node (ref "X2") (pin "13") (pinfunction "GPIO4_13") (pintype "bidirectional"))
    )
    (net (code "44") (name "GPIO5{slash}SCL") (class "Default")
      (node (ref "J1") (pin "6") (pinfunction "6_6") (pintype "passive"))
      (node (ref "X2") (pin "14") (pinfunction "GPIO5_14") (pintype "bidirectional"))
    )
    (net (code "45") (name "GPIO12{slash}MISO") (class "Default")
      (node (ref "J1") (pin "4") (pinfunction "4_4") (pintype "passive"))
      (node (ref "X2") (pin "6") (pinfunction "GPIO12_6") (pintype "bidirectional"))
    )
    (net (code "46") (name "GPIO13{slash}MOSI") (class "Default")
      (node (ref "J1") (pin "3") (pinfunction "3_3") (pintype "passive"))
      (node (ref "X2") (pin "7") (pinfunction "GPIO13_7") (pintype "bidirectional"))
    )
    (net (code "47") (name "GPIO14{slash}SCK") (class "Default")
      (node (ref "J1") (pin "5") (pinfunction "5_5") (pintype "passive"))
      (node (ref "X2") (pin "5") (pinfunction "GPIO14_5") (pintype "bidirectional"))
    )
    (net (code "48") (name "GPIO15") (class "Default")
      (node (ref "Q4") (pin "2") (pinfunction "S_2") (pintype "bidirectional"))
      (node (ref "R1") (pin "1") (pinfunction "1_1") (pintype "passive"))
      (node (ref "V") (pin "1") (pinfunction "1_1") (pintype "passive"))
      (node (ref "X2") (pin "10") (pinfunction "GPIO15_10") (pintype "bidirectional"))
    )
    (net (code "49") (name "GPIO16") (class "Default")
      (node (ref "X2") (pin "4") (pinfunction "GPIO16_4") (pintype "bidirectional"))
    )
    (net (code "50") (name "LDR") (class "Default")
      (node (ref "LDR") (pin "1") (pinfunction "1_1") (pintype "passive"))
      (node (ref "R13") (pin "1") (pinfunction "1_1") (pintype "passive"))
      (node (ref "R14") (pin "2") (pinfunction "2_2") (pintype "passive"))
    )
    (net (code "51") (name "Net-(D1-PadC)") (class "Default")
      (node (ref "D1") (pin "C") (pinfunction "C_C") (pintype "passive"))
      (node (ref "R8") (pin "2") (pinfunction "2_2") (pintype "passive"))
    )
    (net (code "52") (name "Net-(Q1-B)") (class "Default")
      (node (ref "Q1") (pin "1") (pinfunction "B_1") (pintype "passive"))
      (node (ref "R5") (pin "2") (pinfunction "2_2") (pintype "passive"))
    )
    (net (code "53") (name "Net-(Q2-B)") (class "Default")
      (node (ref "Q2") (pin "1") (pinfunction "B_1") (pintype "passive"))
      (node (ref "R7") (pin "2") (pinfunction "2_2") (pintype "passive"))
    )
    (net (code "54") (name "RESET") (class "Default")
      (node (ref "Q1") (pin "3") (pinfunction "C_3") (pintype "passive"))
      (node (ref "R4") (pin "1") (pinfunction "1_1") (pintype "passive"))
      (node (ref "SW2") (pin "B") (pinfunction "S_B") (pintype "passive"))
      (node (ref "SW2") (pin "B'") (pinfunction "S1_B'") (pintype "passive"))
      (node (ref "X2") (pin "1") (pinfunction "RESET_1") (pintype "input"))
    )
    (net (code "55") (name "RTS") (class "Default")
      (node (ref "IC1") (pin "19") (pinfunction "RTS_19") (pintype "output"))
      (node (ref "Q1") (pin "2") (pinfunction "E_2") (pintype "passive"))
      (node (ref "R7") (pin "1") (pinfunction "1_1") (pintype "passive"))
    )
    (net (code "56") (name "RXD") (class "Default")
      (node (ref "R12") (pin "2") (pinfunction "2_2") (pintype "passive"))
      (node (ref "X2") (pin "15") (pinfunction "RXD_15") (pintype "input"))
    )
    (net (code "57") (name "TXD") (class "Default")
      (node (ref "IC1") (pin "20") (pinfunction "RXD_20") (pintype "input"))
      (node (ref "X2") (pin "16") (pinfunction "TXD_16") (pintype "output"))
    )
    (net (code "58") (name "USB_RX") (class "Default")
      (node (ref "IC1") (pin "21") (pinfunction "TXD_21") (pintype "output"))
      (node (ref "R12") (pin "1") (pinfunction "1_1") (pintype "passive"))
    )
    (net (code "59") (name "VBUS") (class "Default")
      (node (ref "C1") (pin "1") (pinfunction "1_1") (pintype "passive"))
      (node (ref "C10") (pin "1") (pinfunction "P$1_1") (pintype "passive"))
      (node (ref "C15") (pin "1") (pinfunction "1_1") (pintype "passive"))
      (node (ref "C16") (pin "1") (pinfunction "1_1") (pintype "passive"))
      (node (ref "C17") (pin "1") (pinfunction "1_1") (pintype "passive"))
      (node (ref "C18") (pin "1") (pinfunction "1_1") (pintype "passive"))
      (node (ref "C19") (pin "1") (pinfunction "1_1") (pintype "passive"))
      (node (ref "C2") (pin "1") (pinfunction "1_1") (pintype "passive"))
      (node (ref "C20") (pin "1") (pinfunction "1_1") (pintype "passive"))
      (node (ref "C21") (pin "1") (pinfunction "1_1") (pintype "passive"))
      (node (ref "C22") (pin "1") (pinfunction "1_1") (pintype "passive"))
      (node (ref "C23") (pin "1") (pinfunction "1_1") (pintype "passive"))
      (node (ref "C24") (pin "1") (pinfunction "1_1") (pintype "passive"))
      (node (ref "C25") (pin "1") (pinfunction "1_1") (pintype "passive"))
      (node (ref "C26") (pin "1") (pinfunction "1_1") (pintype "passive"))
      (node (ref "C27") (pin "1") (pinfunction "1_1") (pintype "passive"))
      (node (ref "C28") (pin "1") (pinfunction "1_1") (pintype "passive"))
      (node (ref "C29") (pin "1") (pinfunction "1_1") (pintype "passive"))
      (node (ref "C3") (pin "1") (pinfunction "1_1") (pintype "passive"))
      (node (ref "C30") (pin "1") (pinfunction "1_1") (pintype "passive"))
      (node (ref "C31") (pin "1") (pinfunction "1_1") (pintype "passive"))
      (node (ref "C32") (pin "1") (pinfunction "1_1") (pintype "passive"))
      (node (ref "C33") (pin "1") (pinfunction "1_1") (pintype "passive"))
      (node (ref "C34") (pin "1") (pinfunction "1_1") (pintype "passive"))
      (node (ref "C35") (pin "1") (pinfunction "1_1") (pintype "passive"))
      (node (ref "C4") (pin "1") (pinfunction "1_1") (pintype "passive"))
      (node (ref "C5") (pin "1") (pinfunction "1_1") (pintype "passive"))
      (node (ref "C6") (pin "1") (pinfunction "1_1") (pintype "passive"))
      (node (ref "C7") (pin "1") (pinfunction "1_1") (pintype "passive"))
      (node (ref "C9") (pin "1") (pinfunction "1_1") (pintype "passive"))
      (node (ref "D1L1") (pin "1-VDD") (pinfunction "VDD_1-VDD") (pintype "power_in"))
      (node (ref "D1L2") (pin "1-VDD") (pinfunction "VDD_1-VDD") (pintype "power_in"))
      (node (ref "D1L3") (pin "1-VDD") (pinfunction "VDD_1-VDD") (pintype "power_in"))
      (node (ref "D1L4") (pin "1-VDD") (pinfunction "VDD_1-VDD") (pintype "power_in"))
      (node (ref "D1L5") (pin "1-VDD") (pinfunction "VDD_1-VDD") (pintype "power_in"))
      (node (ref "D1L6") (pin "1-VDD") (pinfunction "VDD_1-VDD") (pintype "power_in"))
      (node (ref "D1L7") (pin "1-VDD") (pinfunction "VDD_1-VDD") (pintype "power_in"))
      (node (ref "D2L1") (pin "1-VDD") (pinfunction "VDD_1-VDD") (pintype "power_in"))
      (node (ref "D2L2") (pin "1-VDD") (pinfunction "VDD_1-VDD") (pintype "power_in"))
      (node (ref "D2L3") (pin "1-VDD") (pinfunction "VDD_1-VDD") (pintype "power_in"))
      (node (ref "D2L4") (pin "1-VDD") (pinfunction "VDD_1-VDD") (pintype "power_in"))
      (node (ref "D2L5") (pin "1-VDD") (pinfunction "VDD_1-VDD") (pintype "power_in"))
      (node (ref "D2L6") (pin "1-VDD") (pinfunction "VDD_1-VDD") (pintype "power_in"))
      (node (ref "D2L7") (pin "1-VDD") (pinfunction "VDD_1-VDD") (pintype "power_in"))
      (node (ref "D3L1") (pin "1-VDD") (pinfunction "VDD_1-VDD") (pintype "power_in"))
      (node (ref "D3L2") (pin "1-VDD") (pinfunction "VDD_1-VDD") (pintype "power_in"))
      (node (ref "D3L3") (pin "1-VDD") (pinfunction "VDD_1-VDD") (pintype "power_in"))
      (node (ref "D3L4") (pin "1-VDD") (pinfunction "VDD_1-VDD") (pintype "power_in"))
      (node (ref "D3L5") (pin "1-VDD") (pinfunction "VDD_1-VDD") (pintype "power_in"))
      (node (ref "D3L6") (pin "1-VDD") (pinfunction "VDD_1-VDD") (pintype "power_in"))
      (node (ref "D3L7") (pin "1-VDD") (pinfunction "VDD_1-VDD") (pintype "power_in"))
      (node (ref "D4L1") (pin "1-VDD") (pinfunction "VDD_1-VDD") (pintype "power_in"))
      (node (ref "D4L2") (pin "1-VDD") (pinfunction "VDD_1-VDD") (pintype "power_in"))
      (node (ref "D4L3") (pin "1-VDD") (pinfunction "VDD_1-VDD") (pintype "power_in"))
      (node (ref "D4L4") (pin "1-VDD") (pinfunction "VDD_1-VDD") (pintype "power_in"))
      (node (ref "D4L5") (pin "1-VDD") (pinfunction "VDD_1-VDD") (pintype "power_in"))
      (node (ref "D4L6") (pin "1-VDD") (pinfunction "VDD_1-VDD") (pintype "power_in"))
      (node (ref "D4L7") (pin "1-VDD") (pinfunction "VDD_1-VDD") (pintype "power_in"))
      (node (ref "IC1") (pin "8") (pinfunction "VBUS_8") (pintype "power_in"))
      (node (ref "IN") (pin "1") (pinfunction "1_1") (pintype "passive"))
      (node (ref "J1") (pin "9") (pinfunction "9_9") (pintype "passive"))
      (node (ref "LED1") (pin "1-VDD") (pinfunction "VDD_1-VDD") (pintype "power_in"))
      (node (ref "LED2") (pin "1-VDD") (pinfunction "VDD_1-VDD") (pintype "power_in"))
      (node (ref "OUT") (pin "1") (pinfunction "1_1") (pintype "passive"))
      (node (ref "R2") (pin "2") (pinfunction "2_2") (pintype "passive"))
      (node (ref "R6") (pin "2") (pinfunction "2_2") (pintype "passive"))
      (node (ref "R8") (pin "1") (pinfunction "1_1") (pintype "passive"))
      (node (ref "U2") (pin "1") (pinfunction "IN_1") (pintype "power_in"))
      (node (ref "U2") (pin "3") (pinfunction "EN_3") (pintype "input"))
      (node (ref "USB") (pin "VBUS") (pinfunction "VBUS_VBUS") (pintype "power_in"))
    )
    (net (code "60") (name "unconnected-(IC1A-#RST-Pad9)") (class "Default")
      (node (ref "IC1") (pin "9") (pinfunction "#RST_9") (pintype "bidirectional"))
    )
    (net (code "61") (name "unconnected-(IC1A-#SUSPEND-Pad15)") (class "Default")
      (node (ref "IC1") (pin "15") (pinfunction "#SUSPEND_15") (pintype "output"))
    )
    (net (code "62") (name "unconnected-(IC1A-CTS-Pad18)") (class "Default")
      (node (ref "IC1") (pin "18") (pinfunction "CTS_18") (pintype "input"))
    )
    (net (code "63") (name "unconnected-(IC1A-DCD-Pad24)") (class "Default")
      (node (ref "IC1") (pin "24") (pinfunction "DCD_24") (pintype "input"))
    )
    (net (code "64") (name "unconnected-(IC1A-DSR-Pad22)") (class "Default")
      (node (ref "IC1") (pin "22") (pinfunction "DSR_22") (pintype "input"))
    )
    (net (code "65") (name "unconnected-(IC1A-GPIO0{slash}TXLED-Pad14)") (class "Default")
      (node (ref "IC1") (pin "14") (pinfunction "GPIO0/TXLED_14") (pintype "bidirectional"))
    )
    (net (code "66") (name "unconnected-(IC1A-GPIO1{slash}RXLED-Pad13)") (class "Default")
      (node (ref "IC1") (pin "13") (pinfunction "GPIO1/RXLED_13") (pintype "bidirectional"))
    )
    (net (code "67") (name "unconnected-(IC1A-GPIO2-Pad12)") (class "Default")
      (node (ref "IC1") (pin "12") (pinfunction "GPIO2_12") (pintype "bidirectional"))
    )
    (net (code "68") (name "unconnected-(IC1A-GPIO3-Pad11)") (class "Default")
      (node (ref "IC1") (pin "11") (pinfunction "GPIO3_11") (pintype "bidirectional"))
    )
    (net (code "69") (name "unconnected-(IC1A-NC-Pad10)") (class "Default")
      (node (ref "IC1") (pin "10") (pinfunction "NC_10") (pintype "no_connect"))
    )
    (net (code "70") (name "unconnected-(IC1A-RI-Pad1)") (class "Default")
      (node (ref "IC1") (pin "1") (pinfunction "RI_1") (pintype "input"))
    )
    (net (code "71") (name "unconnected-(IC1A-SUSPEND-Pad17)") (class "Default")
      (node (ref "IC1") (pin "17") (pinfunction "SUSPEND_17") (pintype "output"))
    )
    (net (code "72") (name "unconnected-(IC1A-VPP-Pad16)") (class "Default")
      (node (ref "IC1") (pin "16") (pinfunction "VPP_16") (pintype "bidirectional"))
    )
    (net (code "73") (name "unconnected-(U2-P4-Pad4)") (class "Default")
      (node (ref "U2") (pin "4") (pinfunction "P4_4") (pintype "bidirectional"))
    )
    (net (code "74") (name "unconnected-(USB-PadID)") (class "Default")
      (node (ref "USB") (pin "ID") (pinfunction "ID_ID") (pintype "bidirectional"))
    )
    (net (code "75") (name "unconnected-(X2-CLK-Pad20)") (class "Default")
      (node (ref "X2") (pin "20") (pinfunction "CLK_20") (pintype "bidirectional"))
    )
    (net (code "76") (name "unconnected-(X2-CS-Pad17)") (class "Default")
      (node (ref "X2") (pin "17") (pinfunction "CS_17") (pintype "bidirectional"))
    )
    (net (code "77") (name "unconnected-(X2-DI-Pad21)") (class "Default")
      (node (ref "X2") (pin "21") (pinfunction "DI_21") (pintype "bidirectional"))
    )
    (net (code "78") (name "unconnected-(X2-DO-Pad18)") (class "Default")
      (node (ref "X2") (pin "18") (pinfunction "DO_18") (pintype "bidirectional"))
    )
    (net (code "79") (name "unconnected-(X2-GPIO9-Pad22)") (class "Default")
      (node (ref "X2") (pin "22") (pinfunction "GPIO9_22") (pintype "bidirectional"))
    )
    (net (code "80") (name "unconnected-(X2-GPIO10-Pad19)") (class "Default")
      (node (ref "X2") (pin "19") (pinfunction "GPIO10_19") (pintype "bidirectional"))
    )
  )
)
